# blade_design.net
KiCad netlist of a schematic drawn in EAGLE
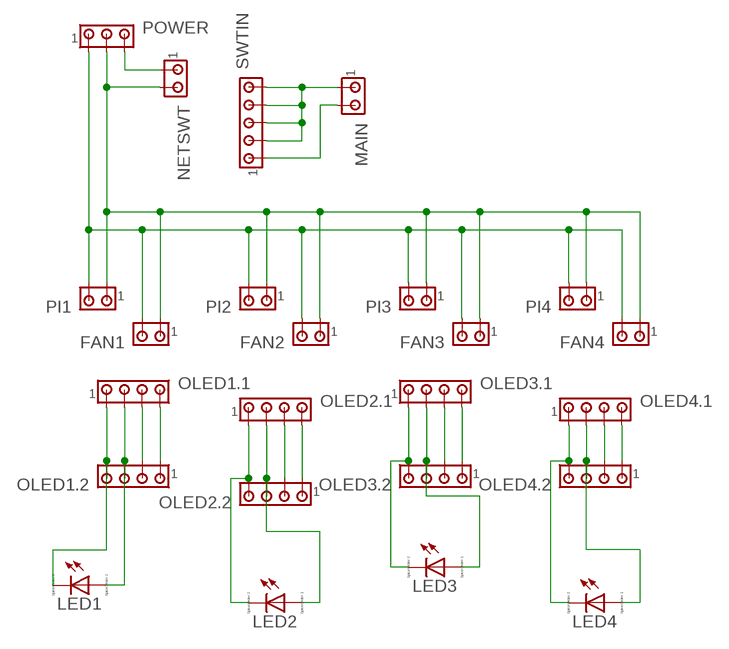
[diagram p0: schematic, sheet 1]

(export (version "E")
  (design (tool "Eeschema 10.0.6"))
  (components
    (comp (ref "FAN1")
      (value "MTA02-156")
      (footprint "eagle-import:1X2MTA")
      (libsource (lib "eagle-import") (part "MTA02-156"))
    )
    (comp (ref "FAN2")
      (value "MTA02-156")
      (footprint "eagle-import:1X2MTA")
      (libsource (lib "eagle-import") (part "MTA02-156"))
    )
    (comp (ref "FAN3")
      (value "MTA02-156")
      (footprint "eagle-import:1X2MTA")
      (libsource (lib "eagle-import") (part "MTA02-156"))
    )
    (comp (ref "FAN4")
      (value "MTA02-156")
      (footprint "eagle-import:1X2MTA")
      (libsource (lib "eagle-import") (part "MTA02-156"))
    )
    (comp (ref "LED1")
      (value "LED_ELD260")
      (footprint "eagle-import:LED_LD260")
      (libsource (lib "eagle-import") (part "LED_ELD260"))
    )
    (comp (ref "LED2")
      (value "LED_ELD260")
      (footprint "eagle-import:LED_LD260")
      (libsource (lib "eagle-import") (part "LED_ELD260"))
    )
    (comp (ref "LED3")
      (value "LED_ELD260")
      (footprint "eagle-import:LED_LD260")
      (libsource (lib "eagle-import") (part "LED_ELD260"))
    )
    (comp (ref "LED4")
      (value "LED_ELD260")
      (footprint "eagle-import:LED_LD260")
      (libsource (lib "eagle-import") (part "LED_ELD260"))
    )
    (comp (ref "MAIN")
      (value "MTA02-156")
      (footprint "eagle-import:1X2MTA")
      (libsource (lib "eagle-import") (part "MTA02-156"))
    )
    (comp (ref "NETSWT")
      (value "MTA02-156")
      (footprint "eagle-import:1X2MTA")
      (libsource (lib "eagle-import") (part "MTA02-156"))
    )
    (comp (ref "OLED1.1")
      (value "MTA04-156")
      (footprint "eagle-import:1X4MTA")
      (libsource (lib "eagle-import") (part "MTA04-156"))
    )
    (comp (ref "OLED1.2")
      (value "MTA04-156")
      (footprint "eagle-import:1X4MTA")
      (libsource (lib "eagle-import") (part "MTA04-156"))
    )
    (comp (ref "OLED2.1")
      (value "MTA04-156")
      (footprint "eagle-import:1X4MTA")
      (libsource (lib "eagle-import") (part "MTA04-156"))
    )
    (comp (ref "OLED2.2")
      (value "MTA04-156")
      (footprint "eagle-import:1X4MTA")
      (libsource (lib "eagle-import") (part "MTA04-156"))
    )
    (comp (ref "OLED3.1")
      (value "MTA04-156")
      (footprint "eagle-import:1X4MTA")
      (libsource (lib "eagle-import") (part "MTA04-156"))
    )
    (comp (ref "OLED3.2")
      (value "MTA04-156")
      (footprint "eagle-import:1X4MTA")
      (libsource (lib "eagle-import") (part "MTA04-156"))
    )
    (comp (ref "OLED4.1")
      (value "MTA04-156")
      (footprint "eagle-import:1X4MTA")
      (libsource (lib "eagle-import") (part "MTA04-156"))
    )
    (comp (ref "OLED4.2")
      (value "MTA04-156")
      (footprint "eagle-import:1X4MTA")
      (libsource (lib "eagle-import") (part "MTA04-156"))
    )
    (comp (ref "PI1")
      (value "MTA02-156")
      (footprint "eagle-import:1X2MTA")
      (libsource (lib "eagle-import") (part "MTA02-156"))
    )
    (comp (ref "PI2")
      (value "MTA02-156")
      (footprint "eagle-import:1X2MTA")
      (libsource (lib "eagle-import") (part "MTA02-156"))
    )
    (comp (ref "PI3")
      (value "MTA02-156")
      (footprint "eagle-import:1X2MTA")
      (libsource (lib "eagle-import") (part "MTA02-156"))
    )
    (comp (ref "PI4")
      (value "MTA02-156")
      (footprint "eagle-import:1X2MTA")
      (libsource (lib "eagle-import") (part "MTA02-156"))
    )
    (comp (ref "POWER")
      (value "MTA03-156")
      (footprint "eagle-import:1X3MTA")
      (libsource (lib "eagle-import") (part "MTA03-156"))
    )
    (comp (ref "SWTIN")
      (value "MTA05-156")
      (footprint "eagle-import:1X5MTA")
      (libsource (lib "eagle-import") (part "MTA05-156"))
    )
  )
  (nets
    (net (code "1") (name "Net-(FAN1-Pad1)") (class "Default")
      (node (ref "FAN1") (pin "1") (pinfunction "1_1") (pintype "passive"))
      (node (ref "FAN2") (pin "1") (pinfunction "1_1") (pintype "passive"))
      (node (ref "FAN3") (pin "1") (pinfunction "1_1") (pintype "passive"))
      (node (ref "FAN4") (pin "1") (pinfunction "1_1") (pintype "passive"))
      (node (ref "NETSWT") (pin "2") (pinfunction "2_2") (pintype "passive"))
      (node (ref "PI1") (pin "1") (pinfunction "1_1") (pintype "passive"))
      (node (ref "PI2") (pin "1") (pinfunction "1_1") (pintype "passive"))
      (node (ref "PI3") (pin "1") (pinfunction "1_1") (pintype "passive"))
      (node (ref "PI4") (pin "1") (pinfunction "1_1") (pintype "passive"))
      (node (ref "POWER") (pin "2") (pinfunction "2_2") (pintype "passive"))
    )
    (net (code "2") (name "Net-(FAN1-Pad2)") (class "Default")
      (node (ref "FAN1") (pin "2") (pinfunction "2_2") (pintype "passive"))
      (node (ref "FAN2") (pin "2") (pinfunction "2_2") (pintype "passive"))
      (node (ref "FAN3") (pin "2") (pinfunction "2_2") (pintype "passive"))
      (node (ref "FAN4") (pin "2") (pinfunction "2_2") (pintype "passive"))
      (node (ref "PI1") (pin "2") (pinfunction "2_2") (pintype "passive"))
      (node (ref "PI2") (pin "2") (pinfunction "2_2") (pintype "passive"))
      (node (ref "PI3") (pin "2") (pinfunction "2_2") (pintype "passive"))
      (node (ref "PI4") (pin "2") (pinfunction "2_2") (pintype "passive"))
      (node (ref "POWER") (pin "1") (pinfunction "1_1") (pintype "passive"))
    )
    (net (code "3") (name "Net-(LED1-C)") (class "Default")
      (node (ref "LED1") (pin "K") (pinfunction "C_K") (pintype "passive"))
      (node (ref "OLED1.1") (pin "1") (pinfunction "1_1") (pintype "passive"))
      (node (ref "OLED1.2") (pin "4") (pinfunction "4_4") (pintype "passive"))
    )
    (net (code "4") (name "Net-(LED1-PadA)") (class "Default")
      (node (ref "LED1") (pin "A") (pinfunction "A_A") (pintype "passive"))
      (node (ref "OLED1.1") (pin "2") (pinfunction "2_2") (pintype "passive"))
      (node (ref "OLED1.2") (pin "3") (pinfunction "3_3") (pintype "passive"))
    )
    (net (code "5") (name "Net-(LED2-C)") (class "Default")
      (node (ref "LED2") (pin "K") (pinfunction "C_K") (pintype "passive"))
      (node (ref "OLED2.1") (pin "1") (pinfunction "1_1") (pintype "passive"))
      (node (ref "OLED2.2") (pin "4") (pinfunction "4_4") (pintype "passive"))
    )
    (net (code "6") (name "Net-(LED2-PadA)") (class "Default")
      (node (ref "LED2") (pin "A") (pinfunction "A_A") (pintype "passive"))
      (node (ref "OLED2.1") (pin "2") (pinfunction "2_2") (pintype "passive"))
      (node (ref "OLED2.2") (pin "3") (pinfunction "3_3") (pintype "passive"))
    )
    (net (code "7") (name "Net-(LED3-C)") (class "Default")
      (node (ref "LED3") (pin "K") (pinfunction "C_K") (pintype "passive"))
      (node (ref "OLED3.1") (pin "1") (pinfunction "1_1") (pintype "passive"))
      (node (ref "OLED3.2") (pin "4") (pinfunction "4_4") (pintype "passive"))
    )
    (net (code "8") (name "Net-(LED3-PadA)") (class "Default")
      (node (ref "LED3") (pin "A") (pinfunction "A_A") (pintype "passive"))
      (node (ref "OLED3.1") (pin "2") (pinfunction "2_2") (pintype "passive"))
      (node (ref "OLED3.2") (pin "3") (pinfunction "3_3") (pintype "passive"))
    )
    (net (code "9") (name "Net-(LED4-C)") (class "Default")
      (node (ref "LED4") (pin "K") (pinfunction "C_K") (pintype "passive"))
      (node (ref "OLED4.1") (pin "1") (pinfunction "1_1") (pintype "passive"))
      (node (ref "OLED4.2") (pin "4") (pinfunction "4_4") (pintype "passive"))
    )
    (net (code "10") (name "Net-(LED4-PadA)") (class "Default")
      (node (ref "LED4") (pin "A") (pinfunction "A_A") (pintype "passive"))
      (node (ref "OLED4.1") (pin "2") (pinfunction "2_2") (pintype "passive"))
      (node (ref "OLED4.2") (pin "3") (pinfunction "3_3") (pintype "passive"))
    )
    (net (code "11") (name "Net-(MAIN-Pad1)") (class "Default")
      (node (ref "MAIN") (pin "1") (pinfunction "1_1") (pintype "passive"))
      (node (ref "SWTIN") (pin "2") (pinfunction "2_2") (pintype "passive"))
      (node (ref "SWTIN") (pin "3") (pinfunction "3_3") (pintype "passive"))
      (node (ref "SWTIN") (pin "4") (pinfunction "4_4") (pintype "passive"))
      (node (ref "SWTIN") (pin "5") (pinfunction "5_5") (pintype "passive"))
    )
    (net (code "12") (name "Net-(MAIN-Pad2)") (class "Default")
      (node (ref "MAIN") (pin "2") (pinfunction "2_2") (pintype "passive"))
      (node (ref "SWTIN") (pin "1") (pinfunction "1_1") (pintype "passive"))
    )
    (net (code "13") (name "Net-(NETSWT-Pad1)") (class "Default")
      (node (ref "NETSWT") (pin "1") (pinfunction "1_1") (pintype "passive"))
      (node (ref "POWER") (pin "3") (pinfunction "3_3") (pintype "passive"))
    )
    (net (code "14") (name "Net-(OLED1.1-Pad3)") (class "Default")
      (node (ref "OLED1.1") (pin "3") (pinfunction "3_3") (pintype "passive"))
      (node (ref "OLED1.2") (pin "2") (pinfunction "2_2") (pintype "passive"))
    )
    (net (code "15") (name "Net-(OLED1.1-Pad4)") (class "Default")
      (node (ref "OLED1.1") (pin "4") (pinfunction "4_4") (pintype "passive"))
      (node (ref "OLED1.2") (pin "1") (pinfunction "1_1") (pintype "passive"))
    )
    (net (code "16") (name "Net-(OLED2.1-Pad3)") (class "Default")
      (node (ref "OLED2.1") (pin "3") (pinfunction "3_3") (pintype "passive"))
      (node (ref "OLED2.2") (pin "2") (pinfunction "2_2") (pintype "passive"))
    )
    (net (code "17") (name "Net-(OLED2.1-Pad4)") (class "Default")
      (node (ref "OLED2.1") (pin "4") (pinfunction "4_4") (pintype "passive"))
      (node (ref "OLED2.2") (pin "1") (pinfunction "1_1") (pintype "passive"))
    )
    (net (code "18") (name "Net-(OLED3.1-Pad3)") (class "Default")
      (node (ref "OLED3.1") (pin "3") (pinfunction "3_3") (pintype "passive"))
      (node (ref "OLED3.2") (pin "2") (pinfunction "2_2") (pintype "passive"))
    )
    (net (code "19") (name "Net-(OLED3.1-Pad4)") (class "Default")
      (node (ref "OLED3.1") (pin "4") (pinfunction "4_4") (pintype "passive"))
      (node (ref "OLED3.2") (pin "1") (pinfunction "1_1") (pintype "passive"))
    )
    (net (code "20") (name "Net-(OLED4.1-Pad3)") (class "Default")
      (node (ref "OLED4.1") (pin "3") (pinfunction "3_3") (pintype "passive"))
      (node (ref "OLED4.2") (pin "2") (pinfunction "2_2") (pintype "passive"))
    )
    (net (code "21") (name "Net-(OLED4.1-Pad4)") (class "Default")
      (node (ref "OLED4.1") (pin "4") (pinfunction "4_4") (pintype "passive"))
      (node (ref "OLED4.2") (pin "1") (pinfunction "1_1") (pintype "passive"))
    )
  )
)
